# USB_HUB.net
KiCad netlist of a schematic drawn in Altium Designer
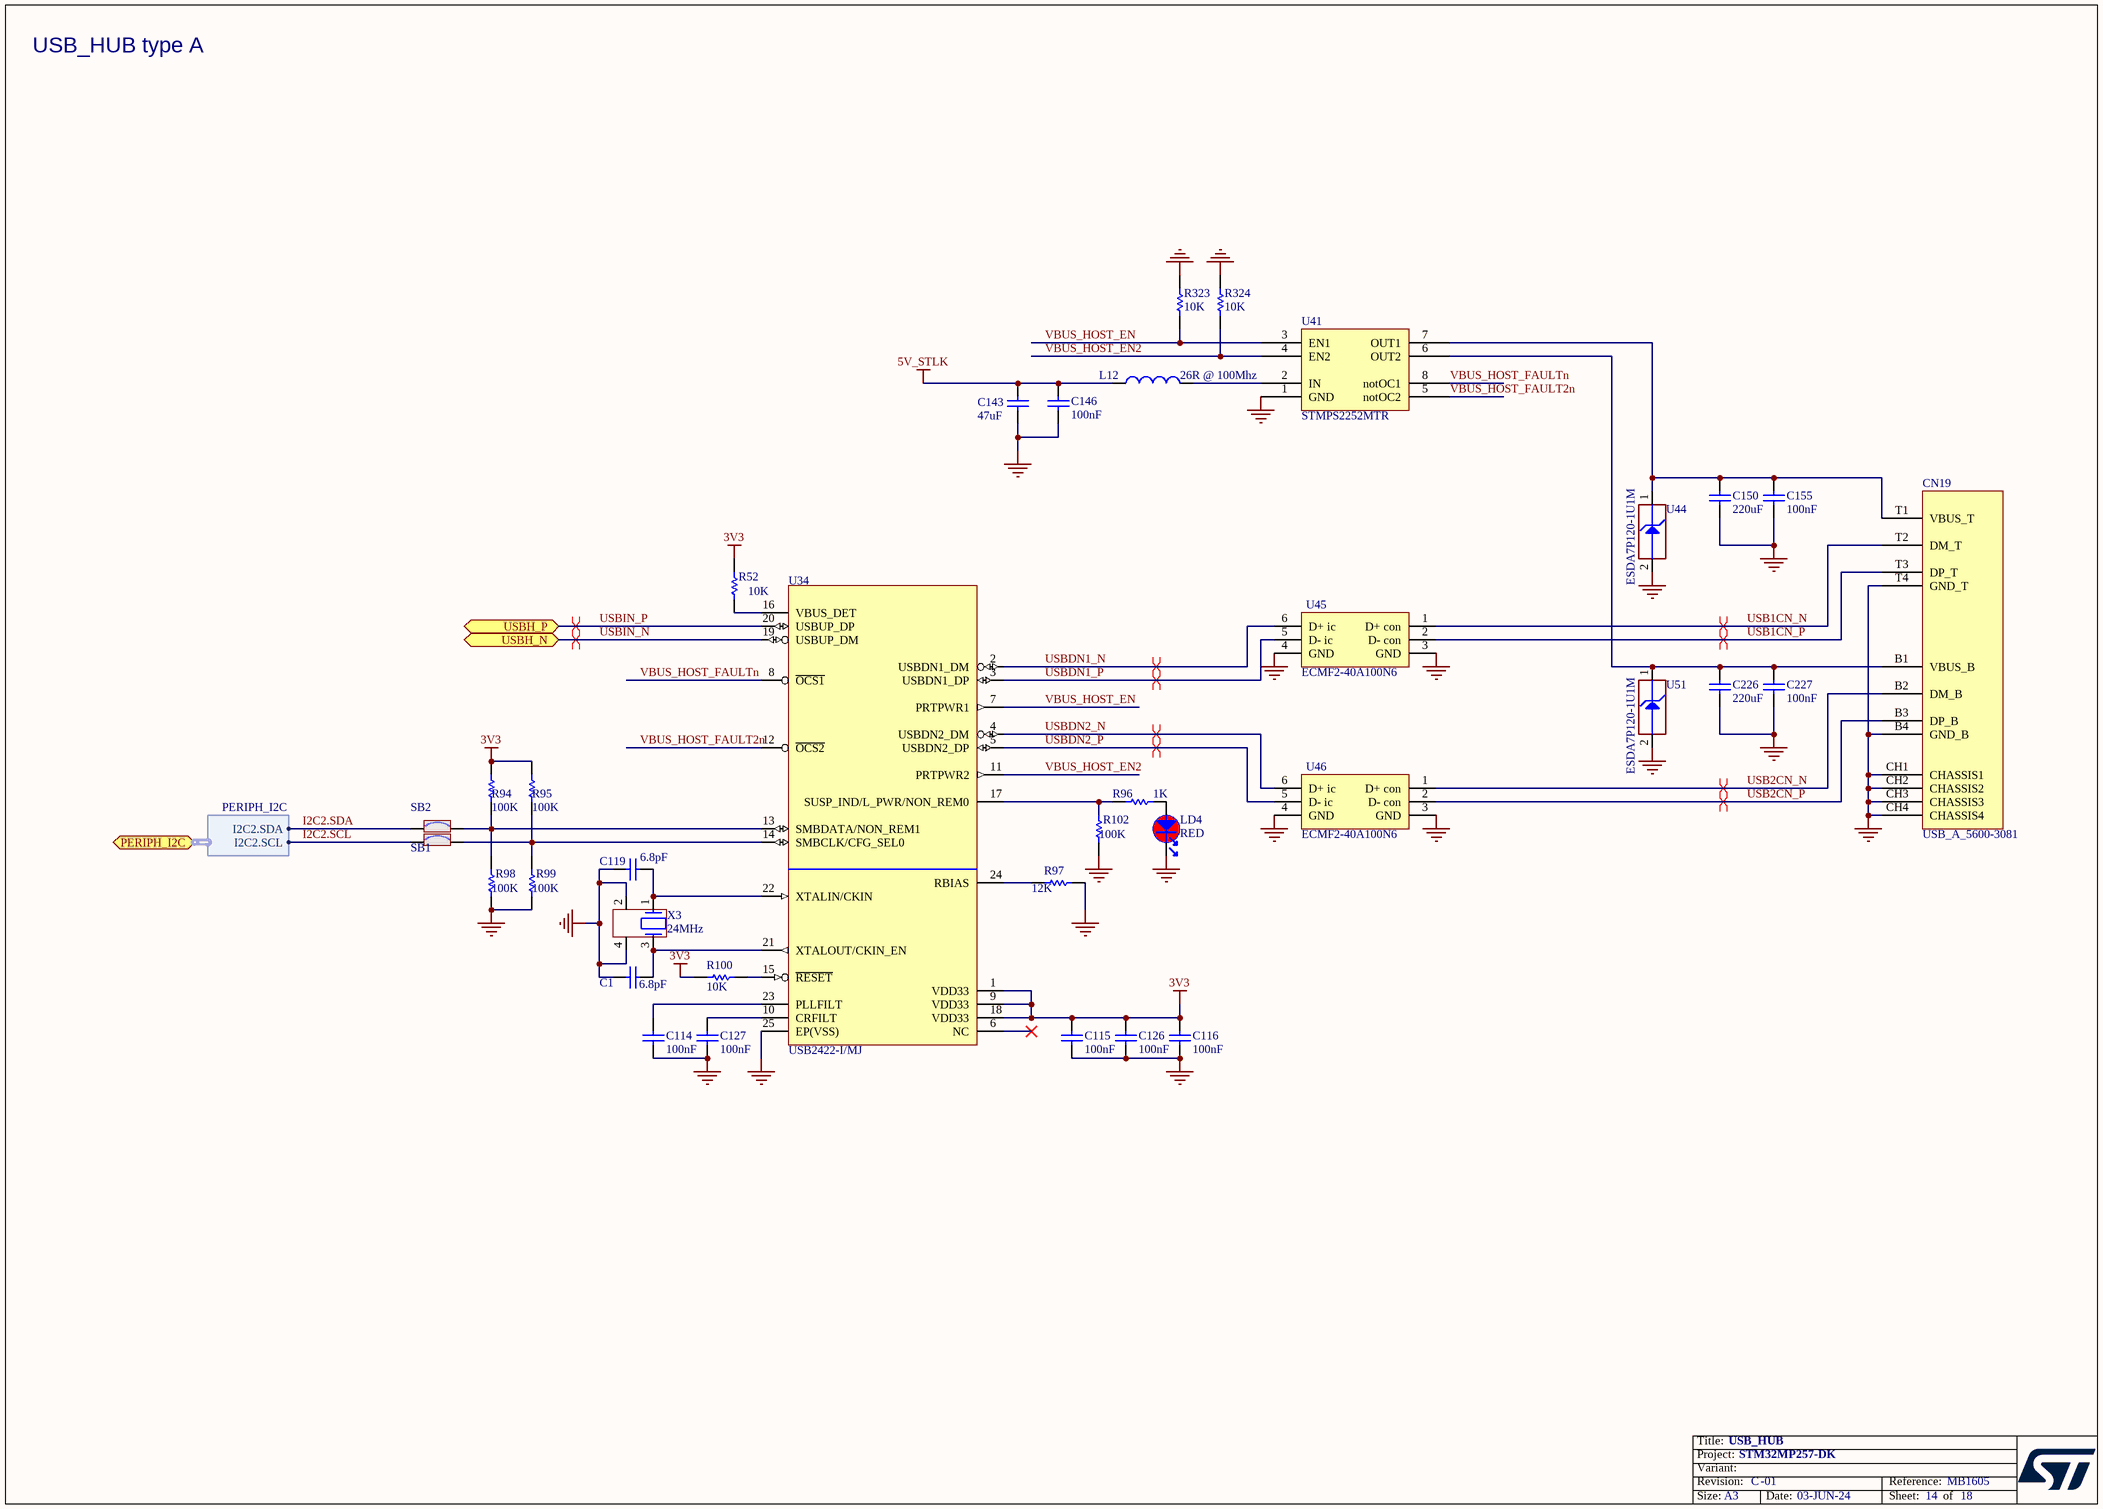
[diagram p0: USB_HUB.SchDoc]

(export (version "E")
  (design (tool "Eeschema 10.0.6"))
  (components
    (comp (ref "C1")
      (value "6.8pF")
      (footprint "C0402")
      (description "Capacitor, MLCC, 6.8pF, 50V, NPO, +-0.25pF, 0402, T=0.5mm")
      (fields
        (field (name "INTERNAL_PART_NUMBER") "MCD-00674")
        (field (name "MANUFACTURER_PART_NUMBER") "CC0402CRNPO9BN6R8")
        (field (name "PROVIDED_BY") "SUBCO")
      )
      (libsource (lib "MCD_PARTS_database") (part "Capacitor"))
    )
    (comp (ref "C114")
      (value "100nF")
      (footprint "C0402")
      (description "Capacitor, MLCC, 100nF, 16V, X7R, +/-10%, 0402, T=0.5mm")
      (fields
        (field (name "INTERNAL_PART_NUMBER") "MCD-00006")
        (field (name "MANUFACTURER_PART_NUMBER") "CC0402KRX7R7BB104")
      )
      (libsource (lib "MCD_PARTS_database") (part "Capacitor"))
    )
    (comp (ref "C115")
      (value "100nF")
      (footprint "C0402")
      (description "Capacitor, MLCC, 100nF, 16V, X7R, +/-10%, 0402, T=0.5mm")
      (fields
        (field (name "INTERNAL_PART_NUMBER") "MCD-00006")
        (field (name "MANUFACTURER_PART_NUMBER") "CC0402KRX7R7BB104")
      )
      (libsource (lib "MCD_PARTS_database") (part "Capacitor"))
    )
    (comp (ref "C116")
      (value "100nF")
      (footprint "C0402")
      (description "Capacitor, MLCC, 100nF, 16V, X7R, +/-10%, 0402, T=0.5mm")
      (fields
        (field (name "INTERNAL_PART_NUMBER") "MCD-00006")
        (field (name "MANUFACTURER_PART_NUMBER") "CC0402KRX7R7BB104")
      )
      (libsource (lib "MCD_PARTS_database") (part "Capacitor"))
    )
    (comp (ref "C119")
      (value "6.8pF")
      (footprint "C0402")
      (description "Capacitor, MLCC, 6.8pF, 50V, NPO, +-0.25pF, 0402, T=0.5mm")
      (fields
        (field (name "INTERNAL_PART_NUMBER") "MCD-00674")
        (field (name "MANUFACTURER_PART_NUMBER") "CC0402CRNPO9BN6R8")
        (field (name "PROVIDED_BY") "SUBCO")
      )
      (libsource (lib "MCD_PARTS_database") (part "Capacitor"))
    )
    (comp (ref "C126")
      (value "100nF")
      (footprint "C0402")
      (description "Capacitor, MLCC, 100nF, 16V, X7R, +/-10%, 0402, T=0.5mm")
      (fields
        (field (name "INTERNAL_PART_NUMBER") "MCD-00006")
        (field (name "MANUFACTURER_PART_NUMBER") "CC0402KRX7R7BB104")
      )
      (libsource (lib "MCD_PARTS_database") (part "Capacitor"))
    )
    (comp (ref "C127")
      (value "100nF")
      (footprint "C0402")
      (description "Capacitor, MLCC, 100nF, 16V, X7R, +/-10%, 0402, T=0.5mm")
      (fields
        (field (name "INTERNAL_PART_NUMBER") "MCD-00006")
        (field (name "MANUFACTURER_PART_NUMBER") "CC0402KRX7R7BB104")
      )
      (libsource (lib "MCD_PARTS_database") (part "Capacitor"))
    )
    (comp (ref "C143")
      (value "47uF")
      (footprint "C0805")
      (description "Capacitor, MLCC, 47uF, 10V, X5R, +/-20%, 0805, T=1.25mm")
      (fields (field (name "INTERNAL_PART_NUMBER") "MCD-00204") (field (name "MANUFACTURER") "MURATA"))
      (libsource (lib "MCD_PARTS_database") (part "Capacitor"))
    )
    (comp (ref "C146")
      (value "100nF")
      (footprint "C0402")
      (description "Capacitor, MLCC, 100nF, 16V, X7R, +/-10%, 0402, T=0.5mm")
      (fields
        (field (name "INTERNAL_PART_NUMBER") "MCD-00006")
        (field (name "MANUFACTURER_PART_NUMBER") "CC0402KRX7R7BB104")
      )
      (libsource (lib "MCD_PARTS_database") (part "Capacitor"))
    )
    (comp (ref "C150")
      (value "220uF")
      (footprint "C1206_H1P6")
      (description "Capacitor, MLCC, 220uF, 6V3, X5R, +/-20%, 1206, T=1.6mm")
      (fields
        (field (name "INTERNAL_PART_NUMBER") "MCD-00104")
        (field (name "MANUFACTURER_PART_NUMBER") "GRM31CR60J227ME11")
      )
      (libsource (lib "MCD_PARTS_database") (part "Capacitor"))
    )
    (comp (ref "C155")
      (value "100nF")
      (footprint "C0402")
      (description "Capacitor, MLCC, 100nF, 16V, X7R, +/-10%, 0402, T=0.5mm")
      (fields
        (field (name "INTERNAL_PART_NUMBER") "MCD-00006")
        (field (name "MANUFACTURER_PART_NUMBER") "CC0402KRX7R7BB104")
      )
      (libsource (lib "MCD_PARTS_database") (part "Capacitor"))
    )
    (comp (ref "C226")
      (value "220uF")
      (footprint "C1206_H1P6")
      (description "Capacitor, MLCC, 220uF, 6V3, X5R, +/-20%, 1206, T=1.6mm")
      (fields
        (field (name "INTERNAL_PART_NUMBER") "MCD-00104")
        (field (name "MANUFACTURER_PART_NUMBER") "GRM31CR60J227ME11")
      )
      (libsource (lib "MCD_PARTS_database") (part "Capacitor"))
    )
    (comp (ref "C227")
      (value "100nF")
      (footprint "C0402")
      (description "Capacitor, MLCC, 100nF, 16V, X7R, +/-10%, 0402, T=0.5mm")
      (fields
        (field (name "INTERNAL_PART_NUMBER") "MCD-00006")
        (field (name "MANUFACTURER_PART_NUMBER") "CC0402KRX7R7BB104")
      )
      (libsource (lib "MCD_PARTS_database") (part "Capacitor"))
    )
    (comp (ref "CN19")
      (value "USB_A_5600-3081")
      (footprint "CON_DUAL-USB-TYPE-A_CONEXCON_5600-3081")
      (description "USB_Dual-TypeA, Receptacle, 8pins, 2.5mm, RA, TH, T= 15.5mm")
      (fields
        (field (name "INTERNAL_PART_NUMBER") "MCD-00109")
        (field (name "MANUFACTURER_PART_NUMBER") "5600-3081")
      )
      (libsource (lib "MCD_PARTS_database") (part "USB_DUAL_TYPEA_5600-3081"))
    )
    (comp (ref "L12")
      (value "26R @ 100Mhz")
      (footprint "FIL_0603_H0P65")
      (description "Ferrite bead, 26R @ 100Mhz, +/-25%, 6000mA, 0R007, 0603, T=0.75mm")
      (fields
        (field (name "INTERNAL_PART_NUMBER") "MCD-00305")
        (field (name "MANUFACTURER_PART_NUMBER") "BLM18KG260TN1")
      )
      (libsource (lib "MCD_PARTS_database") (part "BEAD"))
    )
    (comp (ref "LD4")
      (value "RED")
      (footprint "LED_0603_VISHAY_VLMS1300-GS08_RED_1A2K_H0P8")
      (description "LED Red, 0603 SMD, 2V Forward Voltage")
      (fields
        (field (name "INTERNAL_PART_NUMBER") "MCD-00587")
        (field (name "MANUFACTURER_PART_NUMBER") "VLMS1300-GS08")
        (field (name "PROVIDED_BY") "SUBCO")
      )
      (libsource (lib "MCD_PARTS_database") (part "LED_red"))
    )
    (comp (ref "R52")
      (value "10K")
      (footprint "R0402")
      (description "Resistor,10K,0402,1%,1/16W")
      (fields
        (field (name "INTERNAL_PART_NUMBER") "MCD-00053")
        (field (name "MANUFACTURER_PART_NUMBER") "RC0402FR-0710KL")
        (field (name "PROVIDED_BY") "SUBCO")
      )
      (libsource (lib "MCD_PARTS_database") (part "Resistor"))
    )
    (comp (ref "R94")
      (value "100K")
      (footprint "R0402")
      (description "Resistor,100K,0402,1%,1/16W")
      (fields
        (field (name "INTERNAL_PART_NUMBER") "MCD-00059")
        (field (name "MANUFACTURER_PART_NUMBER") "RC0402FR-07100KL")
        (field (name "PROVIDED_BY") "SUBCO")
      )
      (libsource (lib "MCD_PARTS_database") (part "Resistor"))
    )
    (comp (ref "R95")
      (value "100K")
      (footprint "R0402")
      (description "Resistor,100K,0402,1%,1/16W")
      (fields
        (field (name "INTERNAL_PART_NUMBER") "MCD-00059")
        (field (name "MANUFACTURER_PART_NUMBER") "RC0402FR-07100KL")
        (field (name "PROVIDED_BY") "SUBCO")
      )
      (libsource (lib "MCD_PARTS_database") (part "Resistor"))
    )
    (comp (ref "R96")
      (value "1K")
      (footprint "R0402")
      (description "Resistor,1K,0402,1%,1/16W")
      (fields
        (field (name "INTERNAL_PART_NUMBER") "MCD-00061")
        (field (name "MANUFACTURER_PART_NUMBER") "RC0402FR-071KL")
        (field (name "PROVIDED_BY") "SUBCO")
      )
      (libsource (lib "MCD_PARTS_database") (part "Resistor"))
    )
    (comp (ref "R97")
      (value "12K")
      (footprint "R0402")
      (description "Resistor,12K,0402,1%,1/16W")
      (fields
        (field (name "INTERNAL_PART_NUMBER") "MCD-00187")
        (field (name "MANUFACTURER_PART_NUMBER") "RC0402FR-0712KL")
        (field (name "PROVIDED_BY") "SUBCO")
      )
      (libsource (lib "MCD_PARTS_database") (part "Resistor"))
    )
    (comp (ref "R98")
      (value "100K")
      (footprint "R0402")
      (description "Resistor,100K,0402,1%,1/16W")
      (fields
        (field (name "INTERNAL_PART_NUMBER") "MCD-00059")
        (field (name "MANUFACTURER_PART_NUMBER") "RC0402FR-07100KL")
        (field (name "PROVIDED_BY") "SUBCO")
      )
      (libsource (lib "MCD_PARTS_database") (part "Resistor"))
    )
    (comp (ref "R99")
      (value "100K")
      (footprint "R0402")
      (description "Resistor,100K,0402,1%,1/16W")
      (fields
        (field (name "INTERNAL_PART_NUMBER") "MCD-00059")
        (field (name "MANUFACTURER_PART_NUMBER") "RC0402FR-07100KL")
        (field (name "PROVIDED_BY") "SUBCO")
      )
      (libsource (lib "MCD_PARTS_database") (part "Resistor"))
    )
    (comp (ref "R100")
      (value "10K")
      (footprint "R0402")
      (description "Resistor,10K,0402,1%,1/16W")
      (fields
        (field (name "INTERNAL_PART_NUMBER") "MCD-00053")
        (field (name "MANUFACTURER_PART_NUMBER") "RC0402FR-0710KL")
        (field (name "PROVIDED_BY") "SUBCO")
      )
      (libsource (lib "MCD_PARTS_database") (part "Resistor"))
    )
    (comp (ref "R102")
      (value "100K")
      (footprint "R0402")
      (description "Resistor,100K,0402,1%,1/16W")
      (fields
        (field (name "INTERNAL_PART_NUMBER") "MCD-00059")
        (field (name "MANUFACTURER_PART_NUMBER") "RC0402FR-07100KL")
        (field (name "PROVIDED_BY") "SUBCO")
      )
      (libsource (lib "MCD_PARTS_database") (part "Resistor"))
    )
    (comp (ref "R323")
      (value "10K")
      (footprint "R0402")
      (description "Resistor, 10K, 0402, +/-1%, 1/16W")
      (fields
        (field (name "INTERNAL_PART_NUMBER") "MCD-00053")
        (field (name "MANUFACTURER_PART_NUMBER") "RC0402FR-0710KL")
      )
      (libsource (lib "MCD_PARTS_database") (part "Resistor"))
    )
    (comp (ref "R324")
      (value "10K")
      (footprint "R0402")
      (description "Resistor, 10K, 0402, +/-1%, 1/16W")
      (fields
        (field (name "INTERNAL_PART_NUMBER") "MCD-00053")
        (field (name "MANUFACTURER_PART_NUMBER") "RC0402FR-0710KL")
      )
      (libsource (lib "MCD_PARTS_database") (part "Resistor"))
    )
    (comp (ref "SB1")
      (value "SB_ON")
      (footprint "SOLDER-BRIDGE_R0603-0R")
      (description "Solder Bridge ON")
      (fields (field (name "INTERNAL_PART_NUMBER") "MCD-00071") (field (name "MANUFACTURER") "YAGEO"))
      (libsource (lib "MCD_PARTS_database") (part "SB_ON"))
    )
    (comp (ref "SB2")
      (value "SB_ON")
      (footprint "SOLDER-BRIDGE_R0603-0R")
      (description "Solder Bridge ON")
      (fields (field (name "INTERNAL_PART_NUMBER") "MCD-00071") (field (name "MANUFACTURER") "YAGEO"))
      (libsource (lib "MCD_PARTS_database") (part "SB_ON"))
    )
    (comp (ref "U34")
      (value "USB2422-I/MJ")
      (footprint "ICC_SQFN24-EPAD_4X4_P050")
      (description "2xPort USB 2.0 Hi-Speed Hub Controller")
      (fields (field (name "INTERNAL_PART_NUMBER") "MCD-02348") (field (name "MANUFACTURER") "MICROCHIP"))
      (libsource (lib "MCD_PARTS_database") (part "USB2422-I/MJ"))
    )
    (comp (ref "U41")
      (value "STMPS2252MTR")
      (footprint "ICC_SO8_5X4_P127")
      (description "IC,Dual-Channel-Power-Switch,500mA,100mR,SO8")
      (fields
        (field (name "INTERNAL_PART_NUMBER") "MCD-00123")
        (field (name "MANUFACTURER") "STMICROELECTRONICS")
      )
      (libsource (lib "MCD_PARTS_database") (part "STMPS2252MTR"))
    )
    (comp (ref "U44")
      (value "ESDA7P120-1U1M")
      (footprint "ESD_QFN1610_2N_1K_2A")
      (description "High power transient voltage suppressor")
      (fields
        (field (name "INTERNAL_PART_NUMBER") "MCD-01026")
        (field (name "MANUFACTURER") "STMICROELECTRONICS")
      )
      (libsource (lib "MCD_PARTS_database") (part "ESD-TRANSIL"))
    )
    (comp (ref "U45")
      (value "ECMF2-40A100N6")
      (footprint "ESD_UQFN-6L_1P45X1P4_P040")
      (description "ESD protection & Common Filter High Speed serial Interfaces , 0.4 pitch")
      (fields
        (field (name "INTERNAL_PART_NUMBER") "MCD-03060")
        (field (name "MANUFACTURER") "STMICROELECTRONICS")
      )
      (libsource (lib "MCD_PARTS_database") (part "ECMF2-40A100N6"))
    )
    (comp (ref "U46")
      (value "ECMF2-40A100N6")
      (footprint "ESD_UQFN-6L_1P45X1P4_P040")
      (description "ESD protection & Common Filter High Speed serial Interfaces , 0.4 pitch")
      (fields
        (field (name "INTERNAL_PART_NUMBER") "MCD-03060")
        (field (name "MANUFACTURER") "STMICROELECTRONICS")
      )
      (libsource (lib "MCD_PARTS_database") (part "ECMF2-40A100N6"))
    )
    (comp (ref "U51")
      (value "ESDA7P120-1U1M")
      (footprint "ESD_QFN1610_2N_1K_2A")
      (description "High power transient voltage suppressor")
      (fields
        (field (name "INTERNAL_PART_NUMBER") "MCD-01026")
        (field (name "MANUFACTURER") "STMICROELECTRONICS")
      )
      (libsource (lib "MCD_PARTS_database") (part "ESD-TRANSIL"))
    )
    (comp (ref "X3")
      (value "24MHz")
      (footprint "CRY_NX2016SA_4P")
      (description "Crystal 24MHz, 6pF, +-20ppm, 80ohms max, SMD")
      (fields
        (field (name "INTERNAL_PART_NUMBER") "MCD-01036")
        (field (name "MANUFACTURER_PART_NUMBER") "NX2016SA-24MHZ-EXS00A-CS10820")
        (field (name "PROVIDED_BY") "SUBCO")
      )
      (libsource (lib "MCD_PARTS_database") (part "XTAL_4_PINS"))
    )
  )
  (nets
    (net (code "2") (name "/I2C2.SCL") (class "Default")
      (node (ref "SB1") (pin "1") (pinfunction "1_1") (pintype "passive"))
    )
    (net (code "3") (name "/I2C2.SDA") (class "Default")
      (node (ref "SB2") (pin "1") (pinfunction "1_1") (pintype "passive"))
    )
    (net (code "4") (name "/USB1CN_N") (class "Default")
      (node (ref "CN19") (pin "T2") (pinfunction "DM_T_T2") (pintype "passive"))
      (node (ref "U45") (pin "1") (pinfunction "D+_con_1") (pintype "passive"))
    )
    (net (code "5") (name "/USB1CN_P") (class "Default")
      (node (ref "CN19") (pin "T3") (pinfunction "DP_T_T3") (pintype "passive"))
      (node (ref "U45") (pin "2") (pinfunction "D-_con_2") (pintype "passive"))
    )
    (net (code "6") (name "/USB2CN_N") (class "Default")
      (node (ref "CN19") (pin "B2") (pinfunction "DM_B_B2") (pintype "passive"))
      (node (ref "U46") (pin "1") (pinfunction "D+_con_1") (pintype "passive"))
    )
    (net (code "7") (name "/USB2CN_P") (class "Default")
      (node (ref "CN19") (pin "B3") (pinfunction "DP_B_B3") (pintype "passive"))
      (node (ref "U46") (pin "2") (pinfunction "D-_con_2") (pintype "passive"))
    )
    (net (code "8") (name "/USBDN1_N") (class "Default")
      (node (ref "U34") (pin "2") (pinfunction "USBDN1_DM_2") (pintype "bidirectional"))
      (node (ref "U45") (pin "6") (pinfunction "D+_ic_6") (pintype "passive"))
    )
    (net (code "9") (name "/USBDN1_P") (class "Default")
      (node (ref "U34") (pin "3") (pinfunction "USBDN1_DP_3") (pintype "bidirectional"))
      (node (ref "U45") (pin "5") (pinfunction "D-_ic_5") (pintype "passive"))
    )
    (net (code "10") (name "/USBDN2_N") (class "Default")
      (node (ref "U34") (pin "4") (pinfunction "USBDN2_DM_4") (pintype "bidirectional"))
      (node (ref "U46") (pin "6") (pinfunction "D+_ic_6") (pintype "passive"))
    )
    (net (code "11") (name "/USBDN2_P") (class "Default")
      (node (ref "U34") (pin "5") (pinfunction "USBDN2_DP_5") (pintype "bidirectional"))
      (node (ref "U46") (pin "5") (pinfunction "D-_ic_5") (pintype "passive"))
    )
    (net (code "12") (name "/USBIN_N") (class "Default")
      (node (ref "U34") (pin "19") (pinfunction "USBUP_DM_19") (pintype "bidirectional"))
    )
    (net (code "13") (name "/USBIN_P") (class "Default")
      (node (ref "U34") (pin "20") (pinfunction "USBUP_DP_20") (pintype "bidirectional"))
    )
    (net (code "14") (name "/VBUS_HOST_EN") (class "Default")
      (node (ref "R323") (pin "2") (pinfunction "2_2") (pintype "passive"))
      (node (ref "U34") (pin "7") (pinfunction "PRTPWR1_7") (pintype "output"))
      (node (ref "U41") (pin "3") (pinfunction "EN1_3") (pintype "passive"))
    )
    (net (code "15") (name "/VBUS_HOST_EN2") (class "Default")
      (node (ref "R324") (pin "2") (pinfunction "2_2") (pintype "passive"))
      (node (ref "U34") (pin "11") (pinfunction "PRTPWR2_11") (pintype "output"))
      (node (ref "U41") (pin "4") (pinfunction "EN2_4") (pintype "passive"))
    )
    (net (code "16") (name "/VBUS_HOST_FAULT2n") (class "Default")
      (node (ref "U34") (pin "12") (pinfunction "~{OCS2}_12") (pintype "passive"))
      (node (ref "U41") (pin "5") (pinfunction "notOC2_5") (pintype "passive"))
    )
    (net (code "17") (name "/VBUS_HOST_FAULTn") (class "Default")
      (node (ref "U34") (pin "8") (pinfunction "~{OCS1}_8") (pintype "passive"))
      (node (ref "U41") (pin "8") (pinfunction "notOC1_8") (pintype "passive"))
    )
    (net (code "19") (name "3V3") (class "Default")
      (node (ref "C115") (pin "2") (pinfunction "2_2") (pintype "passive"))
      (node (ref "C116") (pin "2") (pinfunction "2_2") (pintype "passive"))
      (node (ref "C126") (pin "2") (pinfunction "2_2") (pintype "passive"))
      (node (ref "R100") (pin "1") (pinfunction "1_1") (pintype "passive"))
      (node (ref "R52") (pin "2") (pinfunction "2_2") (pintype "passive"))
      (node (ref "R94") (pin "2") (pinfunction "2_2") (pintype "passive"))
      (node (ref "R95") (pin "2") (pinfunction "2_2") (pintype "passive"))
      (node (ref "U34") (pin "1") (pinfunction "VDD33_1") (pintype "power_in"))
      (node (ref "U34") (pin "18") (pinfunction "VDD33_18") (pintype "power_in"))
      (node (ref "U34") (pin "9") (pinfunction "VDD33_9") (pintype "power_in"))
    )
    (net (code "20") (name "5V_STLK") (class "Default")
      (node (ref "C143") (pin "2") (pinfunction "2_2") (pintype "passive"))
      (node (ref "C146") (pin "2") (pinfunction "2_2") (pintype "passive"))
      (node (ref "L12") (pin "1") (pinfunction "1_1") (pintype "passive"))
    )
    (net (code "21") (name "GND") (class "Default")
      (node (ref "C1") (pin "1") (pinfunction "1_1") (pintype "passive"))
      (node (ref "C114") (pin "1") (pinfunction "1_1") (pintype "passive"))
      (node (ref "C115") (pin "1") (pinfunction "1_1") (pintype "passive"))
      (node (ref "C116") (pin "1") (pinfunction "1_1") (pintype "passive"))
      (node (ref "C119") (pin "1") (pinfunction "1_1") (pintype "passive"))
      (node (ref "C126") (pin "1") (pinfunction "1_1") (pintype "passive"))
      (node (ref "C127") (pin "1") (pinfunction "1_1") (pintype "passive"))
      (node (ref "C143") (pin "1") (pinfunction "1_1") (pintype "passive"))
      (node (ref "C146") (pin "1") (pinfunction "1_1") (pintype "passive"))
      (node (ref "C150") (pin "1") (pinfunction "1_1") (pintype "passive"))
      (node (ref "C155") (pin "1") (pinfunction "1_1") (pintype "passive"))
      (node (ref "C226") (pin "1") (pinfunction "1_1") (pintype "passive"))
      (node (ref "C227") (pin "1") (pinfunction "1_1") (pintype "passive"))
      (node (ref "CN19") (pin "B4") (pinfunction "GND_B_B4") (pintype "passive"))
      (node (ref "CN19") (pin "CH1") (pinfunction "CHASSIS1_CH1") (pintype "passive"))
      (node (ref "CN19") (pin "CH2") (pinfunction "CHASSIS2_CH2") (pintype "passive"))
      (node (ref "CN19") (pin "CH3") (pinfunction "CHASSIS3_CH3") (pintype "passive"))
      (node (ref "CN19") (pin "CH4") (pinfunction "CHASSIS4_CH4") (pintype "passive"))
      (node (ref "CN19") (pin "T4") (pinfunction "GND_T_T4") (pintype "passive"))
      (node (ref "LD4") (pin "2") (pintype "passive"))
      (node (ref "R102") (pin "1") (pinfunction "1_1") (pintype "passive"))
      (node (ref "R323") (pin "1") (pinfunction "1_1") (pintype "passive"))
      (node (ref "R324") (pin "1") (pinfunction "1_1") (pintype "passive"))
      (node (ref "R97") (pin "1") (pinfunction "1_1") (pintype "passive"))
      (node (ref "R98") (pin "1") (pinfunction "1_1") (pintype "passive"))
      (node (ref "R99") (pin "1") (pinfunction "1_1") (pintype "passive"))
      (node (ref "U34") (pin "25") (pinfunction "EP(VSS)_25") (pintype "power_in"))
      (node (ref "U41") (pin "1") (pinfunction "GND_1") (pintype "passive"))
      (node (ref "U44") (pin "2") (pinfunction "GND_2") (pintype "passive"))
      (node (ref "U45") (pin "3") (pinfunction "GND_3") (pintype "passive"))
      (node (ref "U45") (pin "4") (pinfunction "GND_4") (pintype "passive"))
      (node (ref "U46") (pin "3") (pinfunction "GND_3") (pintype "passive"))
      (node (ref "U46") (pin "4") (pinfunction "GND_4") (pintype "passive"))
      (node (ref "U51") (pin "2") (pinfunction "GND_2") (pintype "passive"))
      (node (ref "X3") (pin "2") (pinfunction "2_2") (pintype "passive"))
      (node (ref "X3") (pin "4") (pinfunction "4_4") (pintype "passive"))
    )
    (net (code "22") (name "Net-(CN19-VBUS_B)") (class "Default")
      (node (ref "C226") (pin "2") (pinfunction "2_2") (pintype "passive"))
      (node (ref "C227") (pin "2") (pinfunction "2_2") (pintype "passive"))
      (node (ref "CN19") (pin "B1") (pinfunction "VBUS_B_B1") (pintype "passive"))
      (node (ref "U41") (pin "6") (pinfunction "OUT2_6") (pintype "passive"))
      (node (ref "U51") (pin "1") (pinfunction "IO1_1") (pintype "passive"))
    )
    (net (code "23") (name "Net-(CN19-VBUS_T)") (class "Default")
      (node (ref "C150") (pin "2") (pinfunction "2_2") (pintype "passive"))
      (node (ref "C155") (pin "2") (pinfunction "2_2") (pintype "passive"))
      (node (ref "CN19") (pin "T1") (pinfunction "VBUS_T_T1") (pintype "passive"))
      (node (ref "U41") (pin "7") (pinfunction "OUT1_7") (pintype "passive"))
      (node (ref "U44") (pin "1") (pinfunction "IO1_1") (pintype "passive"))
    )
    (net (code "24") (name "Net-(LD4-Pad1)") (class "Default")
      (node (ref "LD4") (pin "1") (pintype "passive"))
      (node (ref "R96") (pin "1") (pinfunction "1_1") (pintype "passive"))
    )
    (net (code "25") (name "Net-(U34-CRFILT)") (class "Default")
      (node (ref "C127") (pin "2") (pinfunction "2_2") (pintype "passive"))
      (node (ref "U34") (pin "10") (pinfunction "CRFILT_10") (pintype "power_in"))
    )
    (net (code "26") (name "Net-(U34-PLLFILT)") (class "Default")
      (node (ref "C114") (pin "2") (pinfunction "2_2") (pintype "passive"))
      (node (ref "U34") (pin "23") (pinfunction "PLLFILT_23") (pintype "power_in"))
    )
    (net (code "27") (name "Net-(U34-RBIAS)") (class "Default")
      (node (ref "R97") (pin "2") (pinfunction "2_2") (pintype "passive"))
      (node (ref "U34") (pin "24") (pinfunction "RBIAS_24") (pintype "passive"))
    )
    (net (code "28") (name "Net-(U34-SMBCLK{slash}CFG_SEL0)") (class "Default")
      (node (ref "R95") (pin "1") (pinfunction "1_1") (pintype "passive"))
      (node (ref "R99") (pin "2") (pinfunction "2_2") (pintype "passive"))
      (node (ref "SB1") (pin "2") (pinfunction "2_2") (pintype "passive"))
      (node (ref "U34") (pin "14") (pinfunction "SMBCLK/CFG_SEL0_14") (pintype "bidirectional"))
    )
    (net (code "29") (name "Net-(U34-SMBDATA{slash}NON_REM1)") (class "Default")
      (node (ref "R94") (pin "1") (pinfunction "1_1") (pintype "passive"))
      (node (ref "R98") (pin "2") (pinfunction "2_2") (pintype "passive"))
      (node (ref "SB2") (pin "2") (pinfunction "2_2") (pintype "passive"))
      (node (ref "U34") (pin "13") (pinfunction "SMBDATA/NON_REM1_13") (pintype "bidirectional"))
    )
    (net (code "30") (name "Net-(U34-SUSP_IND{slash}L_PWR{slash}NON_REM0)") (class "Default")
      (node (ref "R102") (pin "2") (pinfunction "2_2") (pintype "passive"))
      (node (ref "R96") (pin "2") (pinfunction "2_2") (pintype "passive"))
      (node (ref "U34") (pin "17") (pinfunction "SUSP_IND/L_PWR/NON_REM0_17") (pintype "passive"))
    )
    (net (code "31") (name "Net-(U34-VBUS_DET)") (class "Default")
      (node (ref "R52") (pin "1") (pinfunction "1_1") (pintype "passive"))
      (node (ref "U34") (pin "16") (pinfunction "VBUS_DET_16") (pintype "passive"))
    )
    (net (code "32") (name "Net-(U34-XTALIN{slash}CKIN)") (class "Default")
      (node (ref "C119") (pin "2") (pinfunction "2_2") (pintype "passive"))
      (node (ref "U34") (pin "22") (pinfunction "XTALIN/CKIN_22") (pintype "input"))
      (node (ref "X3") (pin "1") (pinfunction "1_1") (pintype "passive"))
    )
    (net (code "33") (name "Net-(U34-XTALOUT{slash}CKIN_EN)") (class "Default")
      (node (ref "C1") (pin "2") (pinfunction "2_2") (pintype "passive"))
      (node (ref "U34") (pin "21") (pinfunction "XTALOUT/CKIN_EN_21") (pintype "output"))
      (node (ref "X3") (pin "3") (pinfunction "3_3") (pintype "passive"))
    )
    (net (code "34") (name "Net-(U34-~{RESET})") (class "Default")
      (node (ref "R100") (pin "2") (pinfunction "2_2") (pintype "passive"))
      (node (ref "U34") (pin "15") (pinfunction "~{RESET}_15") (pintype "input"))
    )
    (net (code "35") (name "Net-(U41-IN)") (class "Default")
      (node (ref "L12") (pin "2") (pinfunction "2_2") (pintype "passive"))
      (node (ref "U41") (pin "2") (pinfunction "IN_2") (pintype "passive"))
    )
    (net (code "36") (name "unconnected-(U34-NC-Pad6)") (class "Default")
      (node (ref "U34") (pin "6") (pinfunction "NC_6") (pintype "power_in+no_connect"))
    )
  )
)
